# itsybitsymo.net
KiCad netlist of a schematic drawn in EAGLE
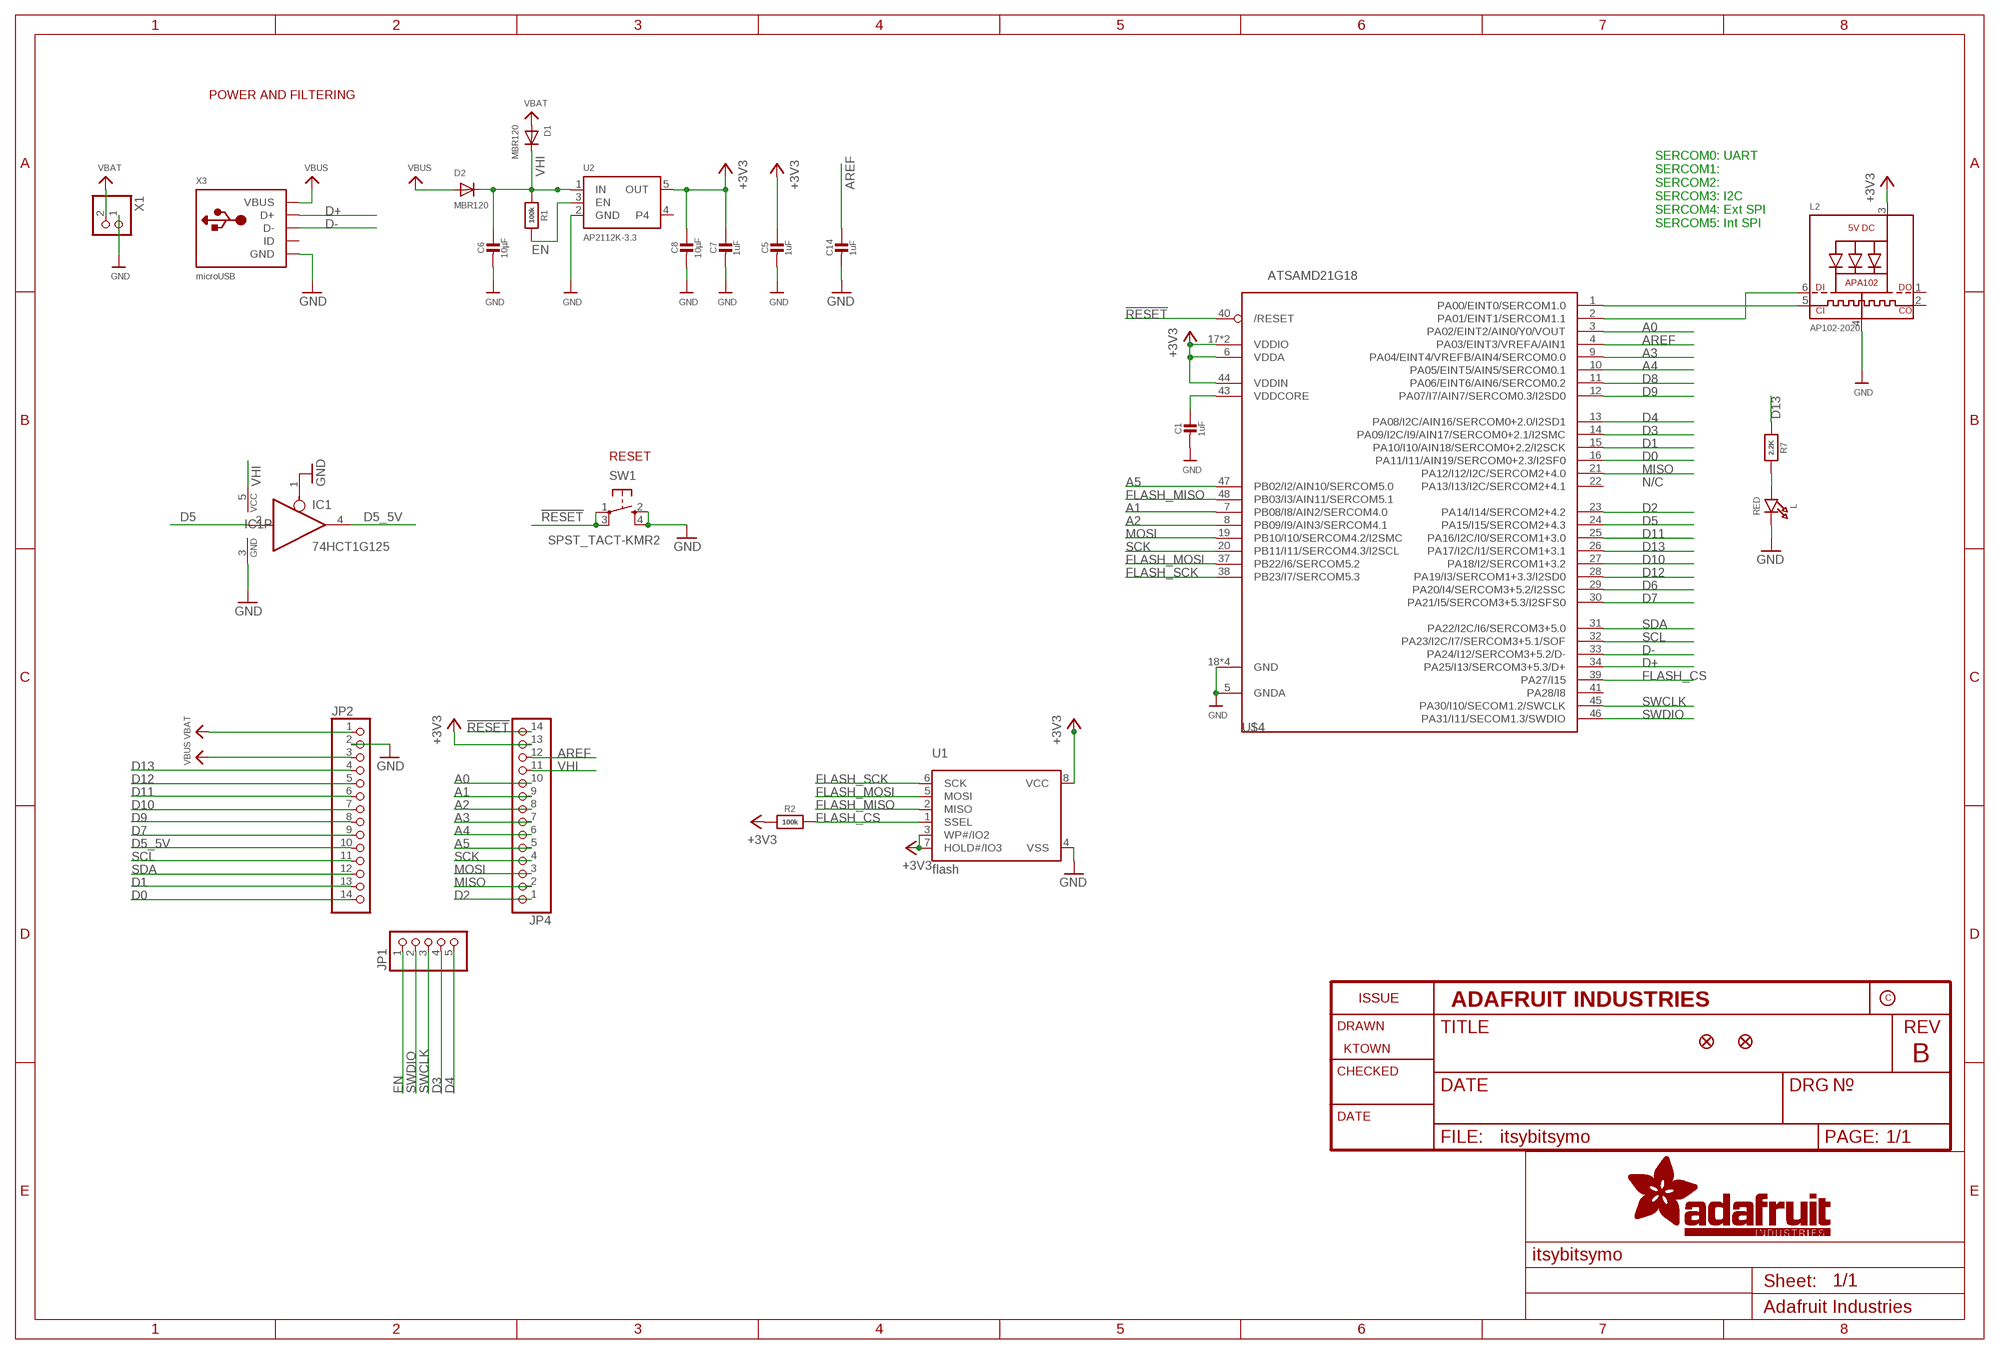
[diagram p0: schematic, sheet 1]

(export (version "E")
  (design (tool "Eeschema 10.0.6"))
  (components
    (comp (ref "C1")
      (value "1uF")
      (footprint "eagle-import:0603-NO")
      (libsource (lib "eagle-import") (part "CAP_CERAMIC0603_NO"))
    )
    (comp (ref "C5")
      (value "1uF")
      (footprint "eagle-import:0603-NO")
      (libsource (lib "eagle-import") (part "CAP_CERAMIC0603_NO"))
    )
    (comp (ref "C6")
      (value "10µF")
      (footprint "eagle-import:0805-NO")
      (libsource (lib "eagle-import") (part "CAP_CERAMIC0805-NOOUTLINE"))
    )
    (comp (ref "C7")
      (value "1uF")
      (footprint "eagle-import:0603-NO")
      (libsource (lib "eagle-import") (part "CAP_CERAMIC0603_NO"))
    )
    (comp (ref "C8")
      (value "10µF")
      (footprint "eagle-import:0805-NO")
      (libsource (lib "eagle-import") (part "CAP_CERAMIC0805-NOOUTLINE"))
    )
    (comp (ref "C14")
      (value "1uF")
      (footprint "eagle-import:0603-NO")
      (libsource (lib "eagle-import") (part "CAP_CERAMIC0603_NO"))
    )
    (comp (ref "D1")
      (value "MBR120")
      (footprint "eagle-import:SOD-123FL")
      (libsource (lib "eagle-import") (part "DIODE_SOD-123FL"))
    )
    (comp (ref "D2")
      (value "MBR120")
      (footprint "eagle-import:SOD-123FL")
      (libsource (lib "eagle-import") (part "DIODE_SOD-123FL"))
    )
    (comp (ref "IC1")
      (value "74HCT1G125")
      (footprint "eagle-import:SOT23-5")
      (libsource (lib "eagle-import") (part "741G125DBVAHC"))
    )
    (comp (ref "JP1")
      (value "HEADER-1X570MIL")
      (footprint "eagle-import:1X05_ROUND_70")
      (libsource (lib "eagle-import") (part "HEADER-1X570MIL"))
    )
    (comp (ref "JP2")
      (value "HEADER-1X14")
      (footprint "eagle-import:1X14_ROUND70")
      (libsource (lib "eagle-import") (part "HEADER-1X14"))
    )
    (comp (ref "JP4")
      (value "HEADER-1X14")
      (footprint "eagle-import:1X14_ROUND70")
      (libsource (lib "eagle-import") (part "HEADER-1X14"))
    )
    (comp (ref "L")
      (value "RED")
      (footprint "eagle-import:CHIPLED_0805_NOOUTLINE")
      (libsource (lib "eagle-import") (part "LED0805_NOOUTLINE"))
    )
    (comp (ref "L2")
      (value "AP102-2020")
      (footprint "eagle-import:APA102_2020")
      (libsource (lib "eagle-import") (part "APA1022020"))
    )
    (comp (ref "R1")
      (value "100k")
      (footprint "eagle-import:0603-NO")
      (libsource (lib "eagle-import") (part "RESISTOR_0603_NOOUT"))
    )
    (comp (ref "R2")
      (value "100k")
      (footprint "eagle-import:0603-NO")
      (libsource (lib "eagle-import") (part "RESISTOR_0603_NOOUT"))
    )
    (comp (ref "R7")
      (value "2.2K")
      (footprint "eagle-import:0603-NO")
      (libsource (lib "eagle-import") (part "RESISTOR_0603_NOOUT"))
    )
    (comp (ref "SW1")
      (value "SPST_TACT-KMR2")
      (footprint "eagle-import:KMR2")
      (libsource (lib "eagle-import") (part "SPST_TACT-KMR2"))
    )
    (comp (ref "U$4")
      (value "ATSAMD21G18")
      (footprint "eagle-import:TQFN48_7MM")
      (libsource (lib "eagle-import") (part "ATSAMD21G_QFN"))
    )
    (comp (ref "U$34")
      (value "FIDUCIAL_1MM")
      (footprint "eagle-import:FIDUCIAL_1MM")
      (libsource (lib "eagle-import") (part "FIDUCIAL_1MM"))
    )
    (comp (ref "U$35")
      (value "FIDUCIAL_1MM")
      (footprint "eagle-import:FIDUCIAL_1MM")
      (libsource (lib "eagle-import") (part "FIDUCIAL_1MM"))
    )
    (comp (ref "U1")
      (value "flash")
      (footprint "eagle-import:USON8")
      (libsource (lib "eagle-import") (part "SPIFLASH_8PINUX"))
    )
    (comp (ref "U2")
      (value "AP2112K-3.3")
      (footprint "eagle-import:SOT23-5")
      (libsource (lib "eagle-import") (part "VREG_SOT23-5"))
    )
    (comp (ref "X1")
      (value "CON_JST_PH_2PIN")
      (footprint "eagle-import:JSTPH2")
      (libsource (lib "eagle-import") (part "CON_JST_PH_2PIN"))
    )
    (comp (ref "X3")
      (value "microUSB")
      (footprint "eagle-import:4UCONN_20329_V2")
      (libsource (lib "eagle-import") (part "USB_MICRO_20329_V2"))
    )
  )
  (nets
    (net (code "1") (name "+3V3") (class "Default")
      (node (ref "C5") (pin "1") (pinfunction "1_1") (pintype "passive"))
      (node (ref "C7") (pin "1") (pinfunction "1_1") (pintype "passive"))
      (node (ref "C8") (pin "1") (pinfunction "1_1") (pintype "passive"))
      (node (ref "JP4") (pin "13") (pinfunction "13_13") (pintype "passive"))
      (node (ref "L2") (pin "3") (pinfunction "VDD_3") (pintype "power_in"))
      (node (ref "R2") (pin "1") (pinfunction "1_1") (pintype "passive"))
      (node (ref "U$4") (pin "17") (pinfunction "VDDIO_17") (pintype "power_in"))
      (node (ref "U$4") (pin "36") (pinfunction "VDDIO_36") (pintype "power_in"))
      (node (ref "U$4") (pin "44") (pinfunction "VDDIN_44") (pintype "power_in"))
      (node (ref "U$4") (pin "6") (pinfunction "VDDA_6") (pintype "power_in"))
      (node (ref "U1") (pin "3") (pinfunction "WP#/IO2_3") (pintype "bidirectional"))
      (node (ref "U1") (pin "7") (pinfunction "HOLD#/IO3_7") (pintype "bidirectional"))
      (node (ref "U1") (pin "8") (pinfunction "VCC_8") (pintype "bidirectional"))
      (node (ref "U2") (pin "5") (pinfunction "OUT_5") (pintype "power_in"))
    )
    (net (code "2") (name "/A0") (class "Default")
      (node (ref "JP4") (pin "10") (pinfunction "10_10") (pintype "passive"))
      (node (ref "U$4") (pin "3") (pinfunction "PA02/EINT2/AIN0/Y0/VOUT_3") (pintype "bidirectional"))
    )
    (net (code "3") (name "/A1") (class "Default")
      (node (ref "JP4") (pin "9") (pinfunction "9_9") (pintype "passive"))
      (node (ref "U$4") (pin "7") (pinfunction "PB08/I8/AIN2/SERCOM4.0_7") (pintype "bidirectional"))
    )
    (net (code "4") (name "/A2") (class "Default")
      (node (ref "JP4") (pin "8") (pinfunction "8_8") (pintype "passive"))
      (node (ref "U$4") (pin "8") (pinfunction "PB09/I9/AIN3/SERCOM4.1_8") (pintype "bidirectional"))
    )
    (net (code "5") (name "/A3") (class "Default")
      (node (ref "JP4") (pin "7") (pinfunction "7_7") (pintype "passive"))
      (node (ref "U$4") (pin "9") (pinfunction "PA04/EINT4/VREFB/AIN4/SERCOM0.0_9") (pintype "bidirectional"))
    )
    (net (code "6") (name "/A4") (class "Default")
      (node (ref "JP4") (pin "6") (pinfunction "6_6") (pintype "passive"))
      (node (ref "U$4") (pin "10") (pinfunction "PA05/EINT5/AIN5/SERCOM0.1_10") (pintype "bidirectional"))
    )
    (net (code "7") (name "/A5") (class "Default")
      (node (ref "JP4") (pin "5") (pinfunction "5_5") (pintype "passive"))
      (node (ref "U$4") (pin "47") (pinfunction "PB02/I2/AIN10/SERCOM5.0_47") (pintype "bidirectional"))
    )
    (net (code "8") (name "/AREF") (class "Default")
      (node (ref "C14") (pin "1") (pinfunction "1_1") (pintype "passive"))
      (node (ref "JP4") (pin "12") (pinfunction "12_12") (pintype "passive"))
      (node (ref "U$4") (pin "4") (pinfunction "PA03/EINT3/VREFA/AIN1_4") (pintype "bidirectional"))
    )
    (net (code "9") (name "/D+") (class "Default")
      (node (ref "U$4") (pin "34") (pinfunction "PA25/I13/SERCOM3+5.3/D+_34") (pintype "bidirectional"))
      (node (ref "X3") (pin "D+") (pinfunction "D+_D+") (pintype "bidirectional"))
    )
    (net (code "10") (name "/D-") (class "Default")
      (node (ref "U$4") (pin "33") (pinfunction "PA24/I12/SERCOM3+5.2/D-_33") (pintype "bidirectional"))
      (node (ref "X3") (pin "D-") (pinfunction "D-_D-") (pintype "bidirectional"))
    )
    (net (code "11") (name "/D0") (class "Default")
      (node (ref "JP2") (pin "14") (pinfunction "14_14") (pintype "passive"))
      (node (ref "U$4") (pin "16") (pinfunction "PA11/I11/AIN19/SERCOM0+2.3/I2SF0_16") (pintype "bidirectional"))
    )
    (net (code "12") (name "/D1") (class "Default")
      (node (ref "JP2") (pin "13") (pinfunction "13_13") (pintype "passive"))
      (node (ref "U$4") (pin "15") (pinfunction "PA10/I10/AIN18/SERCOM0+2.2/I2SCK_15") (pintype "bidirectional"))
    )
    (net (code "13") (name "/D2") (class "Default")
      (node (ref "JP4") (pin "1") (pinfunction "1_1") (pintype "passive"))
      (node (ref "U$4") (pin "23") (pinfunction "PA14/I14/SERCOM2+4.2_23") (pintype "bidirectional"))
    )
    (net (code "14") (name "/D3") (class "Default")
      (node (ref "JP1") (pin "4") (pinfunction "4_4") (pintype "passive"))
      (node (ref "U$4") (pin "14") (pinfunction "PA09/I2C/I9/AIN17/SERCOM0+2.1/I2SMC_14") (pintype "bidirectional"))
    )
    (net (code "15") (name "/D4") (class "Default")
      (node (ref "JP1") (pin "5") (pinfunction "5_5") (pintype "passive"))
      (node (ref "U$4") (pin "13") (pinfunction "PA08/I2C/AIN16/SERCOM0+2.0/I2SD1_13") (pintype "bidirectional"))
    )
    (net (code "16") (name "/D5") (class "Default")
      (node (ref "IC1") (pin "2") (pinfunction "I_2") (pintype "input"))
      (node (ref "U$4") (pin "24") (pinfunction "PA15/I15/SERCOM2+4.3_24") (pintype "bidirectional"))
    )
    (net (code "17") (name "/D5_5V") (class "Default")
      (node (ref "IC1") (pin "4") (pinfunction "O_4") (pintype "tri_state"))
      (node (ref "JP2") (pin "10") (pinfunction "10_10") (pintype "passive"))
    )
    (net (code "18") (name "/D6") (class "Default")
      (node (ref "U$4") (pin "29") (pinfunction "PA20/I4/SERCOM3+5.2/I2SSC_29") (pintype "bidirectional"))
    )
    (net (code "19") (name "/D7") (class "Default")
      (node (ref "JP2") (pin "9") (pinfunction "9_9") (pintype "passive"))
      (node (ref "U$4") (pin "30") (pinfunction "PA21/I5/SERCOM3+5.3/I2SFS0_30") (pintype "bidirectional"))
    )
    (net (code "20") (name "/D8") (class "Default")
      (node (ref "U$4") (pin "11") (pinfunction "PA06/EINT6/AIN6/SERCOM0.2_11") (pintype "bidirectional"))
    )
    (net (code "21") (name "/D9") (class "Default")
      (node (ref "JP2") (pin "8") (pinfunction "8_8") (pintype "passive"))
      (node (ref "U$4") (pin "12") (pinfunction "PA07/I7/AIN7/SERCOM0.3/I2SD0_12") (pintype "bidirectional"))
    )
    (net (code "22") (name "/D10") (class "Default")
      (node (ref "JP2") (pin "7") (pinfunction "7_7") (pintype "passive"))
      (node (ref "U$4") (pin "27") (pinfunction "PA18/I2/SERCOM1+3.2_27") (pintype "bidirectional"))
    )
    (net (code "23") (name "/D11") (class "Default")
      (node (ref "JP2") (pin "6") (pinfunction "6_6") (pintype "passive"))
      (node (ref "U$4") (pin "25") (pinfunction "PA16/I2C/I0/SERCOM1+3.0_25") (pintype "bidirectional"))
    )
    (net (code "24") (name "/D12") (class "Default")
      (node (ref "JP2") (pin "5") (pinfunction "5_5") (pintype "passive"))
      (node (ref "U$4") (pin "28") (pinfunction "PA19/I3/SERCOM1+3.3/I2SD0_28") (pintype "bidirectional"))
    )
    (net (code "25") (name "/D13") (class "Default")
      (node (ref "JP2") (pin "4") (pinfunction "4_4") (pintype "passive"))
      (node (ref "R7") (pin "1") (pinfunction "1_1") (pintype "passive"))
      (node (ref "U$4") (pin "26") (pinfunction "PA17/I2C/I1/SERCOM1+3.1_26") (pintype "bidirectional"))
    )
    (net (code "26") (name "/EN") (class "Default")
      (node (ref "JP1") (pin "1") (pinfunction "1_1") (pintype "passive"))
      (node (ref "R1") (pin "2") (pinfunction "2_2") (pintype "passive"))
      (node (ref "U2") (pin "3") (pinfunction "EN_3") (pintype "input"))
    )
    (net (code "27") (name "/FLASH_CS") (class "Default")
      (node (ref "R2") (pin "2") (pinfunction "2_2") (pintype "passive"))
      (node (ref "U$4") (pin "39") (pinfunction "PA27/I15_39") (pintype "bidirectional"))
      (node (ref "U1") (pin "1") (pinfunction "SSEL_1") (pintype "bidirectional"))
    )
    (net (code "28") (name "/FLASH_MISO") (class "Default")
      (node (ref "U$4") (pin "48") (pinfunction "PB03/I3/AIN11/SERCOM5.1_48") (pintype "bidirectional"))
      (node (ref "U1") (pin "2") (pinfunction "MISO_2") (pintype "bidirectional"))
    )
    (net (code "29") (name "/FLASH_MOSI") (class "Default")
      (node (ref "U$4") (pin "37") (pinfunction "PB22/I6/SERCOM5.2_37") (pintype "bidirectional"))
      (node (ref "U1") (pin "5") (pinfunction "MOSI_5") (pintype "bidirectional"))
    )
    (net (code "30") (name "/FLASH_SCK") (class "Default")
      (node (ref "U$4") (pin "38") (pinfunction "PB23/I7/SERCOM5.3_38") (pintype "bidirectional"))
      (node (ref "U1") (pin "6") (pinfunction "SCK_6") (pintype "bidirectional"))
    )
    (net (code "31") (name "/MISO") (class "Default")
      (node (ref "JP4") (pin "2") (pinfunction "2_2") (pintype "passive"))
      (node (ref "U$4") (pin "21") (pinfunction "PA12/I12/I2C/SERCOM2+4.0_21") (pintype "bidirectional"))
    )
    (net (code "32") (name "/MOSI") (class "Default")
      (node (ref "JP4") (pin "3") (pinfunction "3_3") (pintype "passive"))
      (node (ref "U$4") (pin "19") (pinfunction "PB10/I10/SERCOM4.2/I2SMC_19") (pintype "bidirectional"))
    )
    (net (code "33") (name "/SCK") (class "Default")
      (node (ref "JP4") (pin "4") (pinfunction "4_4") (pintype "passive"))
      (node (ref "U$4") (pin "20") (pinfunction "PB11/I11/SERCOM4.3/I2SCL_20") (pintype "bidirectional"))
    )
    (net (code "34") (name "/SCL") (class "Default")
      (node (ref "JP2") (pin "11") (pinfunction "11_11") (pintype "passive"))
      (node (ref "U$4") (pin "32") (pinfunction "PA23/I2C/I7/SERCOM3+5.1/SOF_32") (pintype "bidirectional"))
    )
    (net (code "35") (name "/SDA") (class "Default")
      (node (ref "JP2") (pin "12") (pinfunction "12_12") (pintype "passive"))
      (node (ref "U$4") (pin "31") (pinfunction "PA22/I2C/I6/SERCOM3+5.0_31") (pintype "bidirectional"))
    )
    (net (code "36") (name "/SWCLK") (class "Default")
      (node (ref "JP1") (pin "3") (pinfunction "3_3") (pintype "passive"))
      (node (ref "U$4") (pin "45") (pinfunction "PA30/I10/SECOM1.2/SWCLK_45") (pintype "bidirectional"))
    )
    (net (code "37") (name "/SWDIO") (class "Default")
      (node (ref "JP1") (pin "2") (pinfunction "2_2") (pintype "passive"))
      (node (ref "U$4") (pin "46") (pinfunction "PA31/I11/SECOM1.3/SWDIO_46") (pintype "bidirectional"))
    )
    (net (code "38") (name "/VHI") (class "Default")
      (node (ref "C6") (pin "1") (pinfunction "1_1") (pintype "passive"))
      (node (ref "D1") (pin "C") (pinfunction "C_C") (pintype "passive"))
      (node (ref "D2") (pin "C") (pinfunction "C_C") (pintype "passive"))
      (node (ref "IC1") (pin "5") (pinfunction "VCC_5") (pintype "power_in"))
      (node (ref "JP4") (pin "11") (pinfunction "11_11") (pintype "passive"))
      (node (ref "R1") (pin "1") (pinfunction "1_1") (pintype "passive"))
      (node (ref "U2") (pin "1") (pinfunction "IN_1") (pintype "power_in"))
    )
    (net (code "39") (name "/~{RESET}") (class "Default")
      (node (ref "JP4") (pin "14") (pinfunction "14_14") (pintype "passive"))
      (node (ref "SW1") (pin "1") (pinfunction "P_1") (pintype "passive"))
      (node (ref "SW1") (pin "3") (pinfunction "P1_3") (pintype "passive"))
      (node (ref "U$4") (pin "40") (pinfunction "/RESET_40") (pintype "bidirectional"))
    )
    (net (code "40") (name "GND") (class "Default")
      (node (ref "C1") (pin "2") (pinfunction "2_2") (pintype "passive"))
      (node (ref "C14") (pin "2") (pinfunction "2_2") (pintype "passive"))
      (node (ref "C5") (pin "2") (pinfunction "2_2") (pintype "passive"))
      (node (ref "C6") (pin "2") (pinfunction "2_2") (pintype "passive"))
      (node (ref "C7") (pin "2") (pinfunction "2_2") (pintype "passive"))
      (node (ref "C8") (pin "2") (pinfunction "2_2") (pintype "passive"))
      (node (ref "IC1") (pin "1") (pinfunction "OE_1") (pintype "input"))
      (node (ref "IC1") (pin "3") (pinfunction "GND_3") (pintype "power_in"))
      (node (ref "JP2") (pin "2") (pinfunction "2_2") (pintype "passive"))
      (node (ref "L") (pin "C") (pinfunction "C_C") (pintype "passive"))
      (node (ref "L2") (pin "4") (pinfunction "GND_4") (pintype "power_in"))
      (node (ref "SW1") (pin "2") (pinfunction "S_2") (pintype "passive"))
      (node (ref "SW1") (pin "4") (pinfunction "S1_4") (pintype "passive"))
      (node (ref "U$4") (pin "18") (pinfunction "GND_18") (pintype "power_in"))
      (node (ref "U$4") (pin "35") (pinfunction "GND_35") (pintype "power_in"))
      (node (ref "U$4") (pin "42") (pinfunction "GND_42") (pintype "power_in"))
      (node (ref "U$4") (pin "5") (pinfunction "GNDA_5") (pintype "power_in"))
      (node (ref "U$4") (pin "THERMAL") (pinfunction "GND_THERMAL") (pintype "power_in"))
      (node (ref "U1") (pin "4") (pinfunction "VSS_4") (pintype "bidirectional"))
      (node (ref "U2") (pin "2") (pinfunction "GND_2") (pintype "power_in"))
      (node (ref "X1") (pin "1") (pinfunction "1_1") (pintype "passive"))
      (node (ref "X3") (pin "BASE@1") (pinfunction "GND_BASE@1") (pintype "power_in"))
      (node (ref "X3") (pin "BASE@2") (pinfunction "GND_BASE@2") (pintype "power_in"))
      (node (ref "X3") (pin "GND") (pinfunction "GND_GND") (pintype "power_in"))
      (node (ref "X3") (pin "SPRT@1") (pinfunction "GND_SPRT@1") (pintype "power_in"))
      (node (ref "X3") (pin "SPRT@2") (pinfunction "GND_SPRT@2") (pintype "power_in"))
      (node (ref "X3") (pin "SPRT@3") (pinfunction "GND_SPRT@3") (pintype "power_in"))
      (node (ref "X3") (pin "SPRT@4") (pinfunction "GND_SPRT@4") (pintype "power_in"))
    )
    (net (code "41") (name "Net-(L-PadA)") (class "Default")
      (node (ref "L") (pin "A") (pinfunction "A_A") (pintype "passive"))
      (node (ref "R7") (pin "2") (pinfunction "2_2") (pintype "passive"))
    )
    (net (code "42") (name "Net-(L2-CKI)") (class "Default")
      (node (ref "L2") (pin "5") (pinfunction "CKI_5") (pintype "input"))
      (node (ref "U$4") (pin "1") (pinfunction "PA00/EINT0/SERCOM1.0_1") (pintype "bidirectional"))
    )
    (net (code "43") (name "Net-(L2-DI)") (class "Default")
      (node (ref "L2") (pin "6") (pinfunction "DI_6") (pintype "input"))
      (node (ref "U$4") (pin "2") (pinfunction "PA01/EINT1/SERCOM1.1_2") (pintype "bidirectional"))
    )
    (net (code "44") (name "Net-(U$4-VDDCORE)") (class "Default")
      (node (ref "C1") (pin "1") (pinfunction "1_1") (pintype "passive"))
      (node (ref "U$4") (pin "43") (pinfunction "VDDCORE_43") (pintype "power_in"))
    )
    (net (code "45") (name "VBAT") (class "Default")
      (node (ref "D1") (pin "A") (pinfunction "A_A") (pintype "passive"))
      (node (ref "JP2") (pin "1") (pinfunction "1_1") (pintype "passive"))
      (node (ref "X1") (pin "2") (pinfunction "2_2") (pintype "passive"))
    )
    (net (code "46") (name "VBUS") (class "Default")
      (node (ref "D2") (pin "A") (pinfunction "A_A") (pintype "passive"))
      (node (ref "JP2") (pin "3") (pinfunction "3_3") (pintype "passive"))
      (node (ref "X3") (pin "VBUS") (pinfunction "VBUS_VBUS") (pintype "power_in"))
    )
    (net (code "47") (name "unconnected-(L2-CKO-Pad2)") (class "Default")
      (node (ref "L2") (pin "2") (pinfunction "CKO_2") (pintype "output"))
    )
    (net (code "48") (name "unconnected-(L2-DO-Pad1)") (class "Default")
      (node (ref "L2") (pin "1") (pinfunction "DO_1") (pintype "output"))
    )
    (net (code "49") (name "unconnected-(U$4-PA13{slash}I13{slash}I2C{slash}SERCOM2+4.1-Pad22)") (class "Default")
      (node (ref "U$4") (pin "22") (pinfunction "PA13/I13/I2C/SERCOM2+4.1_22") (pintype "bidirectional"))
    )
    (net (code "50") (name "unconnected-(U$4-PA28{slash}I8-Pad41)") (class "Default")
      (node (ref "U$4") (pin "41") (pinfunction "PA28/I8_41") (pintype "bidirectional"))
    )
    (net (code "51") (name "unconnected-(U2-P4-Pad4)") (class "Default")
      (node (ref "U2") (pin "4") (pinfunction "P4_4") (pintype "bidirectional"))
    )
    (net (code "52") (name "unconnected-(X3-PadID)") (class "Default")
      (node (ref "X3") (pin "ID") (pinfunction "ID_ID") (pintype "bidirectional"))
    )
  )
)
